# RF.net
KiCad netlist of a schematic drawn in Altium Designer
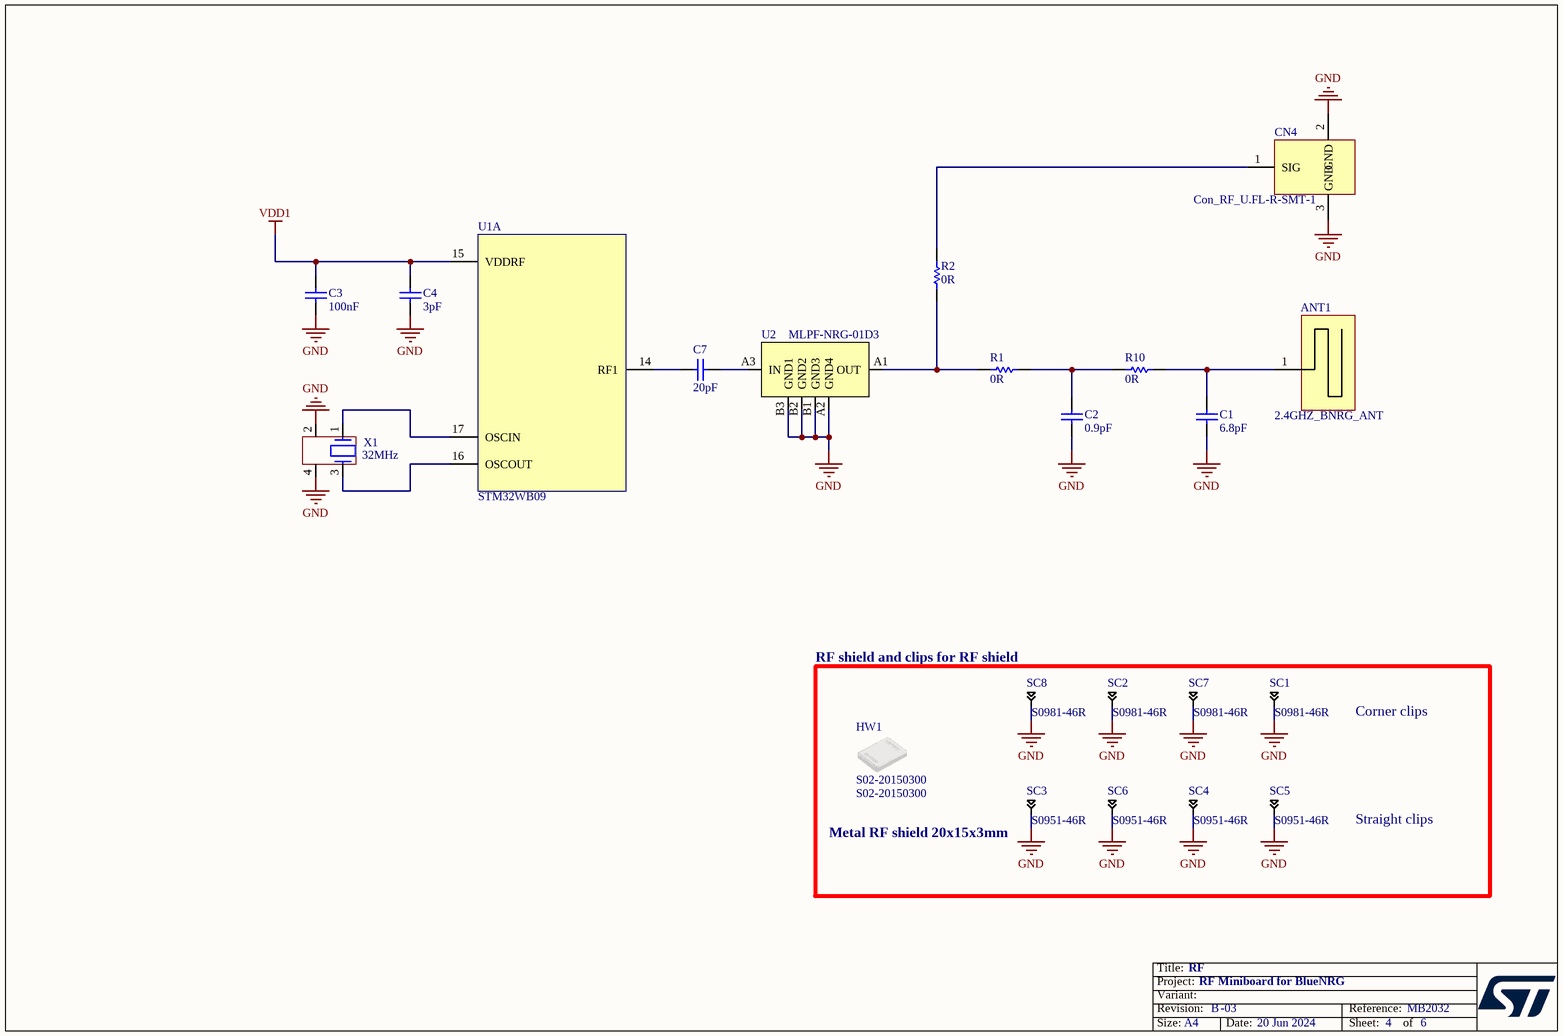
[diagram p0: RF.SchDoc]

(export (version "E")
  (design (tool "Eeschema 10.0.6"))
  (components
    (comp (ref "ANT1")
      (value "2.4GHZ_BNRG_ANT")
      (footprint "MCD_PARTS:ANT_BT_BNRG_2P4GHZ_MB2032")
      (description "2.4 GHZ Bluetooth BNRG PCB antenna")
      (fields (field (name "INTERNAL_PART_NUMBER") "MCD-03495") (field (name "Comment") "2.4GHz_BT_ANT"))
      (libsource (lib "MCD_PARTS_database") (part "2.4GHz_BT_ANT"))
    )
    (comp (ref "C1")
      (value "6.8pF")
      (footprint "MCD_PARTS:C0402")
      (description "Capacitor, MLCC, 6.8pF, 50V, C0G, +/-0.05pF, 0402, T=0.5mm")
      (fields (field (name "INTERNAL_PART_NUMBER") "MCD-03452") (field (name "MANUFACTURER") "MURATA"))
      (libsource (lib "MCD_PARTS_database") (part "Capacitor"))
    )
    (comp (ref "C2")
      (value "0.9pF")
      (footprint "C0402_MURATA_GJM155_H0P5")
      (description "Capacitor, MLCC, 0.9pF, 50V, COG, +/-0.05pF, 0402, T=0.5mm")
      (fields (field (name "INTERNAL_PART_NUMBER") "MCD-04106") (field (name "MANUFACTURER") "MURATA"))
      (libsource (lib "MCD_PARTS_database") (part "Capacitor"))
    )
    (comp (ref "C3")
      (value "100nF")
      (footprint "MCD_PARTS:C0402")
      (description "Capacitor, MLCC, 100nF, ±10%, X7R, 25V, 0402, T=0.5mm")
      (fields (field (name "INTERNAL_PART_NUMBER") "MCD-03442") (field (name "MANUFACTURER") "MURATA"))
      (libsource (lib "MCD_PARTS_database") (part "Capacitor"))
    )
    (comp (ref "C4")
      (value "3pF")
      (footprint "C0402")
      (description "Capacitor, C0G, 3 pF, 50V, NPO, ±0.1pF, 0402, T=0.5mm")
      (fields
        (field (name "INTERNAL_PART_NUMBER") "MCD-03898")
        (field (name "MANUFACTURER") "WALSIN TECHNOLOGY CORPORATION")
      )
      (libsource (lib "MCD_PARTS_database") (part "Capacitor"))
    )
    (comp (ref "C7")
      (value "20pF")
      (footprint "MCD_PARTS:C0201_H0P3")
      (description "Capacitor, MLCC, 20pF, 25V, COG, +/-2%, 0201, T=0.33mm")
      (fields (field (name "INTERNAL_PART_NUMBER") "MCD-03543") (field (name "MANUFACTURER") "MURATA"))
      (libsource (lib "MCD_PARTS_database") (part "Capacitor"))
    )
    (comp (ref "CN4")
      (value "Con_RF_U.FL-R-SMT-1")
      (footprint "MCD_PARTS:CON_HRS_U.FL-R-SMT-1")
      (description "Connector_RF, 0Hz to 6GHz, 50R, VR, SMD, T= 1.25mm")
      (fields (field (name "INTERNAL_PART_NUMBER") "MCD-01583") (field (name "BMS_PART_NUMBER") "9187005"))
      (libsource (lib "MCD_PARTS_database") (part "U.FL-R-SMT-1"))
    )
    (comp (ref "HW1")
      (value "S02-20150300")
      (footprint "MCD_PARTS:SHIELD_HARWIN_S02-20150300_15X20_H3")
      (description "RFI shield can, 20x15x3mm")
      (fields
        (field (name "INTERNAL_PART_NUMBER") "MCD-03126")
        (field (name "ALTIUM_VALUE") "S02-20150300")
        (field (name "MANUFACTURER") "HARWIN")
      )
      (libsource (lib "MCD_PARTS_database") (part "S02-20150300"))
    )
    (comp (ref "R1")
      (value "0R")
      (footprint "MCD_PARTS:R0402")
      (description "Resistor, 0R, 0402, +/-5%, 1/16W")
      (fields (field (name "INTERNAL_PART_NUMBER") "MCD-00052") (field (name "MANUFACTURER") "YAGEO"))
      (libsource (lib "MCD_PARTS_database") (part "Resistor"))
    )
    (comp (ref "R2")
      (value "0R")
      (footprint "MCD_PARTS:r0402")
      (description "Resistor, 0R, 0402, +/-5%, 1/16W")
      (fields (field (name "INTERNAL_PART_NUMBER") "MCD-00052") (field (name "MANUFACTURER") "YAGEO"))
      (libsource (lib "MCD_PARTS_database") (part "Resistor"))
    )
    (comp (ref "R10")
      (value "0R")
      (footprint "MCD_PARTS:R0402")
      (description "Resistor, 0R, 0402, +/-5%, 1/16W")
      (fields (field (name "INTERNAL_PART_NUMBER") "MCD-00052") (field (name "MANUFACTURER") "YAGEO"))
      (libsource (lib "MCD_PARTS_database") (part "Resistor"))
    )
    (comp (ref "SC1")
      (value "S0981-46R")
      (footprint "MCD_PARTS:CLIP_HARWIN_S0981-46R")
      (description "shield clip Harwin S0981-46R to fix RF shielded cavity - SMT RFI Shield Clip, Corner (T+R)")
      (fields (field (name "INTERNAL_PART_NUMBER") "MCD-02164") (field (name "MANUFACTURER") "HARWIN"))
      (libsource (lib "MCD_PARTS_database") (part "Shield-clip_S0951-46R"))
    )
    (comp (ref "SC2")
      (value "S0981-46R")
      (footprint "MCD_PARTS:CLIP_HARWIN_S0981-46R")
      (description "shield clip Harwin S0981-46R to fix RF shielded cavity - SMT RFI Shield Clip, Corner (T+R)")
      (fields (field (name "INTERNAL_PART_NUMBER") "MCD-02164") (field (name "MANUFACTURER") "HARWIN"))
      (libsource (lib "MCD_PARTS_database") (part "Shield-clip_S0951-46R"))
    )
    (comp (ref "SC3")
      (value "S0951-46R")
      (footprint "MCD_PARTS:CLIP_HARWIN_S0951-46R")
      (description "shield clip Harwin S0951-46R to fix RF shielded cavity")
      (fields (field (name "INTERNAL_PART_NUMBER") "MCD-01587") (field (name "MANUFACTURER") "HARWIN"))
      (libsource (lib "MCD_PARTS_database") (part "Shield-clip_S0951-46R"))
    )
    (comp (ref "SC4")
      (value "S0951-46R")
      (footprint "MCD_PARTS:CLIP_HARWIN_S0951-46R")
      (description "shield clip Harwin S0951-46R to fix RF shielded cavity")
      (fields (field (name "INTERNAL_PART_NUMBER") "MCD-01587") (field (name "MANUFACTURER") "HARWIN"))
      (libsource (lib "MCD_PARTS_database") (part "Shield-clip_S0951-46R"))
    )
    (comp (ref "SC5")
      (value "S0951-46R")
      (footprint "MCD_PARTS:CLIP_HARWIN_S0951-46R")
      (description "shield clip Harwin S0951-46R to fix RF shielded cavity")
      (fields (field (name "INTERNAL_PART_NUMBER") "MCD-01587") (field (name "MANUFACTURER") "HARWIN"))
      (libsource (lib "MCD_PARTS_database") (part "Shield-clip_S0951-46R"))
    )
    (comp (ref "SC6")
      (value "S0951-46R")
      (footprint "MCD_PARTS:CLIP_HARWIN_S0951-46R")
      (description "shield clip Harwin S0951-46R to fix RF shielded cavity")
      (fields (field (name "INTERNAL_PART_NUMBER") "MCD-01587") (field (name "MANUFACTURER") "HARWIN"))
      (libsource (lib "MCD_PARTS_database") (part "Shield-clip_S0951-46R"))
    )
    (comp (ref "SC7")
      (value "S0981-46R")
      (footprint "MCD_PARTS:CLIP_HARWIN_S0981-46R")
      (description "shield clip Harwin S0981-46R to fix RF shielded cavity - SMT RFI Shield Clip, Corner (T+R)")
      (fields (field (name "INTERNAL_PART_NUMBER") "MCD-02164") (field (name "MANUFACTURER") "HARWIN"))
      (libsource (lib "MCD_PARTS_database") (part "Shield-clip_S0951-46R"))
    )
    (comp (ref "SC8")
      (value "S0981-46R")
      (footprint "MCD_PARTS:CLIP_HARWIN_S0981-46R")
      (description "shield clip Harwin S0981-46R to fix RF shielded cavity - SMT RFI Shield Clip, Corner (T+R)")
      (fields (field (name "INTERNAL_PART_NUMBER") "MCD-02164") (field (name "MANUFACTURER") "HARWIN"))
      (libsource (lib "MCD_PARTS_database") (part "Shield-clip_S0951-46R"))
    )
    (comp (ref "U1")
      (value "STM32WB09")
      (footprint "ICC_QFN32-EPAD_5X5_P050")
      (description "Bluetooth® Low Energy wireless SoC")
      (fields
        (field (name "INTERNAL_PART_NUMBER") "MCD-03444")
        (field (name "MANUFACTURER") "STMICROELECTRONICS")
      )
      (libsource (lib "MCD_PARTS_database") (part "STM32WB09"))
    )
    (comp (ref "U2")
      (value "MLPF-NRG-01D3")
      (footprint "MCD_PARTS:ICC_CSPG_6BUMPS_1X1P60_P050-P0577")
      (description "2.4 GHz low pass filter matched to BLUENRG-LP-LPS")
      (fields
        (field (name "INTERNAL_PART_NUMBER") "MCD-03490")
        (field (name "MANUFACTURER") "STMICROELECTRONICS")
      )
      (libsource (lib "MCD_PARTS_database") (part "MLPF-WB55-01E3"))
    )
    (comp (ref "X1")
      (value "32MHz")
      (footprint "MCD_PARTS:CRY_NX2016SA_4P")
      (description "Crystal, 32MHz, 8pF, +/-10ppm, 60R, 2x1.6mm")
      (fields (field (name "INTERNAL_PART_NUMBER") "MCD-01446") (field (name "BMS_PART_NUMBER") "9157042"))
      (libsource (lib "MCD_PARTS_database") (part "XTAL_4_PINS"))
    )
  )
  (nets
    (net (code "1") (name "GND") (class "Default")
      (node (ref "C1") (pin "1") (pinfunction "1_1") (pintype "passive"))
      (node (ref "C2") (pin "1") (pinfunction "1_1") (pintype "passive"))
      (node (ref "C3") (pin "1") (pinfunction "1_1") (pintype "passive"))
      (node (ref "C4") (pin "1") (pinfunction "1_1") (pintype "passive"))
      (node (ref "CN4") (pin "2") (pinfunction "GND_2") (pintype "passive"))
      (node (ref "CN4") (pin "3") (pinfunction "GND_3") (pintype "passive"))
      (node (ref "SC1") (pin "1") (pinfunction "1_1") (pintype "passive"))
      (node (ref "SC2") (pin "1") (pinfunction "1_1") (pintype "passive"))
      (node (ref "SC3") (pin "1") (pinfunction "1_1") (pintype "passive"))
      (node (ref "SC4") (pin "1") (pinfunction "1_1") (pintype "passive"))
      (node (ref "SC5") (pin "1") (pinfunction "1_1") (pintype "passive"))
      (node (ref "SC6") (pin "1") (pinfunction "1_1") (pintype "passive"))
      (node (ref "SC7") (pin "1") (pinfunction "1_1") (pintype "passive"))
      (node (ref "SC8") (pin "1") (pinfunction "1_1") (pintype "passive"))
      (node (ref "U2") (pin "A2") (pinfunction "GND4_A2") (pintype "passive"))
      (node (ref "U2") (pin "B1") (pinfunction "GND3_B1") (pintype "passive"))
      (node (ref "U2") (pin "B2") (pinfunction "GND2_B2") (pintype "passive"))
      (node (ref "U2") (pin "B3") (pinfunction "GND1_B3") (pintype "passive"))
      (node (ref "X1") (pin "2") (pinfunction "2_2") (pintype "passive"))
      (node (ref "X1") (pin "4") (pinfunction "4_4") (pintype "passive"))
    )
    (net (code "2") (name "Net-(ANT1-Pad1)") (class "Default")
      (node (ref "ANT1") (pin "1") (pintype "passive"))
      (node (ref "C1") (pin "2") (pinfunction "2_2") (pintype "passive"))
      (node (ref "R10") (pin "2") (pinfunction "2_2") (pintype "passive"))
    )
    (net (code "3") (name "Net-(C2-Pad2)") (class "Default")
      (node (ref "C2") (pin "2") (pinfunction "2_2") (pintype "passive"))
      (node (ref "R1") (pin "2") (pinfunction "2_2") (pintype "passive"))
      (node (ref "R10") (pin "1") (pinfunction "1_1") (pintype "passive"))
    )
    (net (code "4") (name "Net-(CN4-SIG)") (class "Default")
      (node (ref "CN4") (pin "1") (pinfunction "SIG_1") (pintype "passive"))
      (node (ref "R2") (pin "2") (pinfunction "2_2") (pintype "passive"))
    )
    (net (code "5") (name "Net-(U1A-OSCIN)") (class "Default")
      (node (ref "U1") (pin "17") (pinfunction "OSCIN_17") (pintype "passive"))
      (node (ref "X1") (pin "1") (pinfunction "1_1") (pintype "passive"))
    )
    (net (code "6") (name "Net-(U1A-OSCOUT)") (class "Default")
      (node (ref "U1") (pin "16") (pinfunction "OSCOUT_16") (pintype "passive"))
      (node (ref "X1") (pin "3") (pinfunction "3_3") (pintype "passive"))
    )
    (net (code "7") (name "Net-(U1A-RF1)") (class "Default")
      (node (ref "C7") (pin "1") (pinfunction "1_1") (pintype "passive"))
      (node (ref "U1") (pin "14") (pinfunction "RF1_14") (pintype "passive"))
    )
    (net (code "8") (name "Net-(U2-IN)") (class "Default")
      (node (ref "C7") (pin "2") (pinfunction "2_2") (pintype "passive"))
      (node (ref "U2") (pin "A3") (pinfunction "IN_A3") (pintype "passive"))
    )
    (net (code "9") (name "Net-(U2-OUT)") (class "Default")
      (node (ref "R1") (pin "1") (pinfunction "1_1") (pintype "passive"))
      (node (ref "R2") (pin "1") (pinfunction "1_1") (pintype "passive"))
      (node (ref "U2") (pin "A1") (pinfunction "OUT_A1") (pintype "passive"))
    )
    (net (code "10") (name "VDD1") (class "Default")
      (node (ref "C3") (pin "2") (pinfunction "2_2") (pintype "passive"))
      (node (ref "C4") (pin "2") (pinfunction "2_2") (pintype "passive"))
      (node (ref "U1") (pin "15") (pinfunction "VDDRF_15") (pintype "passive"))
    )
  )
)
